# Mainboard.net
KiCad netlist of a schematic drawn in Altium Designer
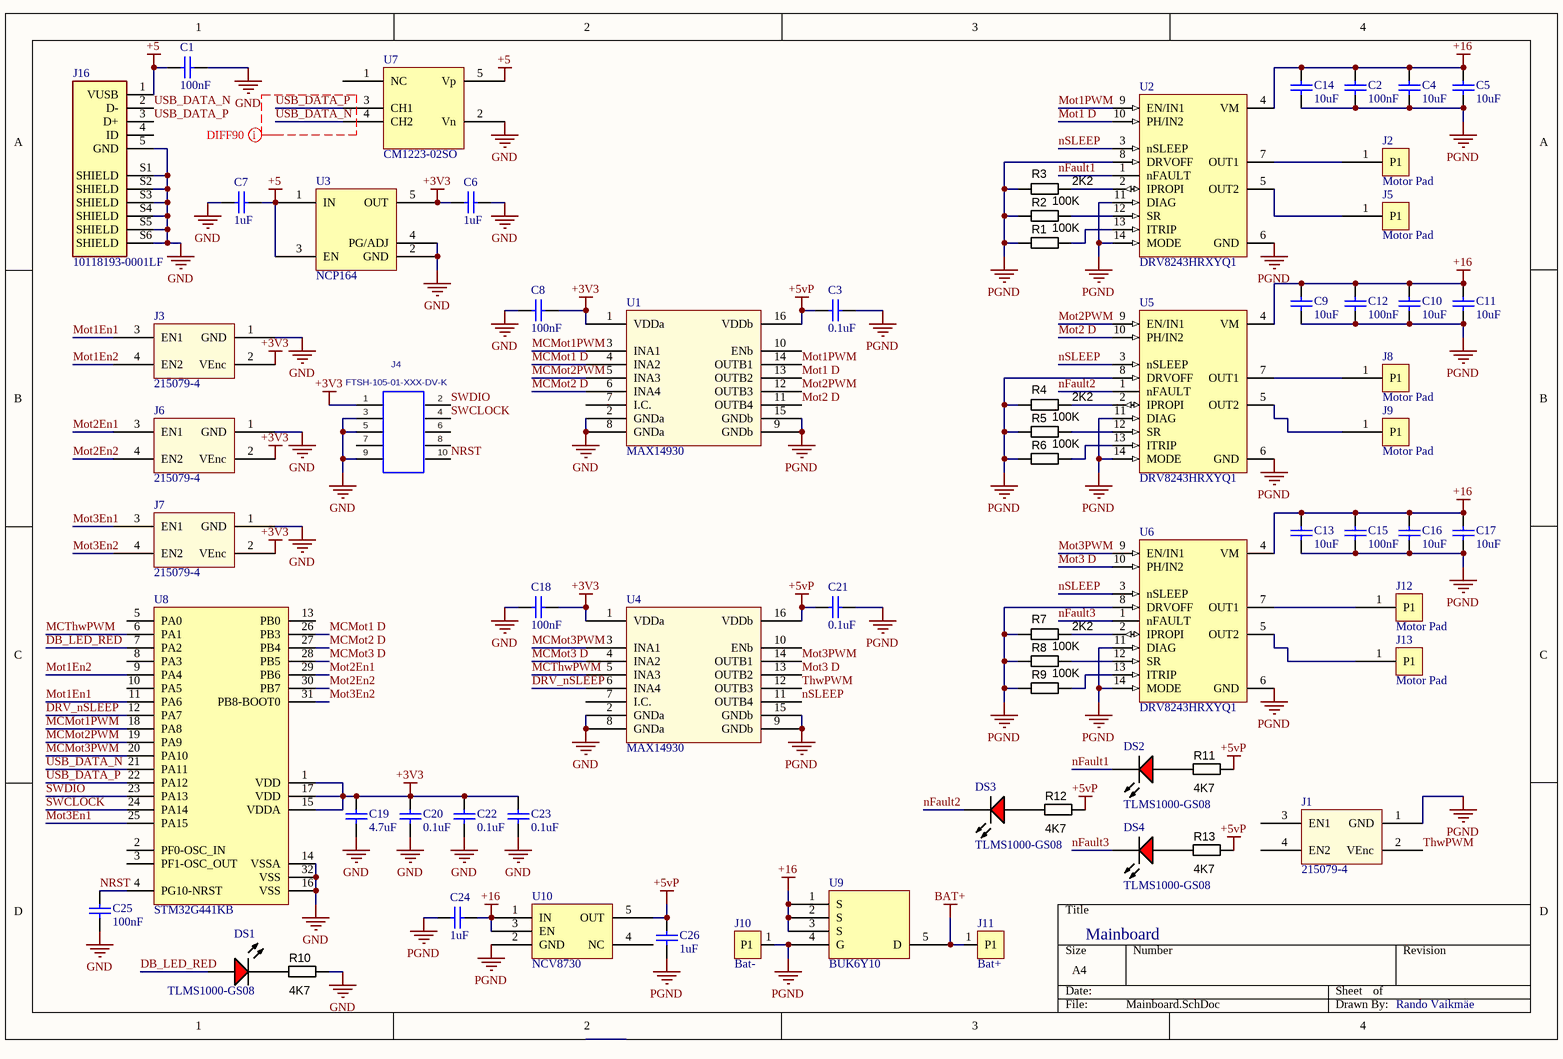
[diagram p0: Mainboard.SchDoc]

(export (version "E")
  (design (tool "Eeschema 10.0.6"))
  (components
    (comp (ref "C1")
      (value "100nF")
      (footprint "1608[0603]")
      (description "Capacitor (Semiconductor SIM Model)")
      (fields (field (name "Comment") "Cap Semi") (field (name "PUBLISHER") "Altium Limited"))
      (libsource (lib "Miscellaneous Devices") (part "Cap Semi"))
    )
    (comp (ref "C2")
      (value "100nF")
      (footprint "1608[0603]")
      (description "Capacitor (Semiconductor SIM Model)")
      (fields (field (name "Comment") "Cap Semi") (field (name "PUBLISHER") "Altium Limited"))
      (libsource (lib "Miscellaneous Devices") (part "Cap Semi"))
    )
    (comp (ref "C3")
      (value "0.1uF")
      (footprint "1608[0603]")
      (description "Capacitor (Semiconductor SIM Model)")
      (fields (field (name "Comment") "Cap Semi") (field (name "PUBLISHER") "Altium Limited"))
      (libsource (lib "Miscellaneous Devices") (part "Cap Semi"))
    )
    (comp (ref "C4")
      (value "10uF")
      (footprint "C1206")
      (description "Capacitor (Semiconductor SIM Model)")
      (fields (field (name "Comment") "Cap Semi") (field (name "PUBLISHER") "Altium Limited"))
      (libsource (lib "Miscellaneous Devices") (part "Cap Semi"))
    )
    (comp (ref "C5")
      (value "10uF")
      (footprint "C1206")
      (description "Capacitor (Semiconductor SIM Model)")
      (fields (field (name "Comment") "Cap Semi") (field (name "PUBLISHER") "Altium Limited"))
      (libsource (lib "Miscellaneous Devices") (part "Cap Semi"))
    )
    (comp (ref "C6")
      (value "1uF")
      (footprint "1608[0603]")
      (description "Capacitor (Semiconductor SIM Model)")
      (fields (field (name "Comment") "Cap Semi") (field (name "PUBLISHER") "Altium Limited"))
      (libsource (lib "Miscellaneous Devices") (part "Cap Semi"))
    )
    (comp (ref "C7")
      (value "1uF")
      (footprint "1608[0603]")
      (description "Capacitor (Semiconductor SIM Model)")
      (fields (field (name "Comment") "Cap Semi") (field (name "PUBLISHER") "Altium Limited"))
      (libsource (lib "Miscellaneous Devices") (part "Cap Semi"))
    )
    (comp (ref "C8")
      (value "100nF")
      (footprint "1608[0603]")
      (description "Capacitor (Semiconductor SIM Model)")
      (fields (field (name "Comment") "Cap Semi") (field (name "PUBLISHER") "Altium Limited"))
      (libsource (lib "Miscellaneous Devices") (part "Cap Semi"))
    )
    (comp (ref "C9")
      (value "10uF")
      (footprint "C1206")
      (description "Capacitor (Semiconductor SIM Model)")
      (fields (field (name "Comment") "Cap Semi") (field (name "PUBLISHER") "Altium Limited"))
      (libsource (lib "Miscellaneous Devices") (part "Cap Semi"))
    )
    (comp (ref "C10")
      (value "10uF")
      (footprint "C1206")
      (description "Capacitor (Semiconductor SIM Model)")
      (fields (field (name "Comment") "Cap Semi") (field (name "PUBLISHER") "Altium Limited"))
      (libsource (lib "Miscellaneous Devices") (part "Cap Semi"))
    )
    (comp (ref "C11")
      (value "10uF")
      (footprint "C1206")
      (description "Capacitor (Semiconductor SIM Model)")
      (fields (field (name "Comment") "Cap Semi") (field (name "PUBLISHER") "Altium Limited"))
      (libsource (lib "Miscellaneous Devices") (part "Cap Semi"))
    )
    (comp (ref "C12")
      (value "100nF")
      (footprint "1608[0603]")
      (description "Capacitor (Semiconductor SIM Model)")
      (fields (field (name "Comment") "Cap Semi") (field (name "PUBLISHER") "Altium Limited"))
      (libsource (lib "Miscellaneous Devices") (part "Cap Semi"))
    )
    (comp (ref "C13")
      (value "10uF")
      (footprint "C1206")
      (description "Capacitor (Semiconductor SIM Model)")
      (fields (field (name "Comment") "Cap Semi") (field (name "PUBLISHER") "Altium Limited"))
      (libsource (lib "Miscellaneous Devices") (part "Cap Semi"))
    )
    (comp (ref "C14")
      (value "10uF")
      (footprint "C1206")
      (description "Capacitor (Semiconductor SIM Model)")
      (fields (field (name "Comment") "Cap Semi") (field (name "PUBLISHER") "Altium Limited"))
      (libsource (lib "Miscellaneous Devices") (part "Cap Semi"))
    )
    (comp (ref "C15")
      (value "100nF")
      (footprint "1608[0603]")
      (description "Capacitor (Semiconductor SIM Model)")
      (fields (field (name "Comment") "Cap Semi") (field (name "PUBLISHER") "Altium Limited"))
      (libsource (lib "Miscellaneous Devices") (part "Cap Semi"))
    )
    (comp (ref "C16")
      (value "10uF")
      (footprint "C1206")
      (description "Capacitor (Semiconductor SIM Model)")
      (fields (field (name "Comment") "Cap Semi") (field (name "PUBLISHER") "Altium Limited"))
      (libsource (lib "Miscellaneous Devices") (part "Cap Semi"))
    )
    (comp (ref "C17")
      (value "10uF")
      (footprint "C1206")
      (description "Capacitor (Semiconductor SIM Model)")
      (fields (field (name "Comment") "Cap Semi") (field (name "PUBLISHER") "Altium Limited"))
      (libsource (lib "Miscellaneous Devices") (part "Cap Semi"))
    )
    (comp (ref "C18")
      (value "100nF")
      (footprint "1608[0603]")
      (description "Capacitor (Semiconductor SIM Model)")
      (fields (field (name "Comment") "Cap Semi") (field (name "PUBLISHER") "Altium Limited"))
      (libsource (lib "Miscellaneous Devices") (part "Cap Semi"))
    )
    (comp (ref "C19")
      (value "4.7uF")
      (footprint "1608[0603]")
      (description "Capacitor (Semiconductor SIM Model)")
      (fields (field (name "Comment") "Cap Semi") (field (name "PUBLISHER") "Altium Limited"))
      (libsource (lib "Miscellaneous Devices") (part "Cap Semi"))
    )
    (comp (ref "C20")
      (value "0.1uF")
      (footprint "1608[0603]")
      (description "Capacitor (Semiconductor SIM Model)")
      (fields (field (name "Comment") "Cap Semi") (field (name "PUBLISHER") "Altium Limited"))
      (libsource (lib "Miscellaneous Devices") (part "Cap Semi"))
    )
    (comp (ref "C21")
      (value "0.1uF")
      (footprint "1608[0603]")
      (description "Capacitor (Semiconductor SIM Model)")
      (fields (field (name "Comment") "Cap Semi") (field (name "PUBLISHER") "Altium Limited"))
      (libsource (lib "Miscellaneous Devices") (part "Cap Semi"))
    )
    (comp (ref "C22")
      (value "0.1uF")
      (footprint "1608[0603]")
      (description "Capacitor (Semiconductor SIM Model)")
      (fields (field (name "Comment") "Cap Semi") (field (name "PUBLISHER") "Altium Limited"))
      (libsource (lib "Miscellaneous Devices") (part "Cap Semi"))
    )
    (comp (ref "C23")
      (value "0.1uF")
      (footprint "1608[0603]")
      (description "Capacitor (Semiconductor SIM Model)")
      (fields (field (name "Comment") "Cap Semi") (field (name "PUBLISHER") "Altium Limited"))
      (libsource (lib "Miscellaneous Devices") (part "Cap Semi"))
    )
    (comp (ref "C24")
      (value "1uF")
      (footprint "1608[0603]")
      (description "Capacitor (Semiconductor SIM Model)")
      (fields (field (name "Comment") "Cap Semi") (field (name "PUBLISHER") "Altium Limited"))
      (libsource (lib "Miscellaneous Devices") (part "Cap Semi"))
    )
    (comp (ref "C25")
      (value "100nF")
      (footprint "1608[0603]")
      (description "Capacitor (Semiconductor SIM Model)")
      (fields (field (name "Comment") "Cap Semi") (field (name "PUBLISHER") "Altium Limited"))
      (libsource (lib "Miscellaneous Devices") (part "Cap Semi"))
    )
    (comp (ref "C26")
      (value "1uF")
      (footprint "1608[0603]")
      (description "Capacitor (Semiconductor SIM Model)")
      (fields (field (name "Comment") "Cap Semi") (field (name "PUBLISHER") "Altium Limited"))
      (libsource (lib "Miscellaneous Devices") (part "Cap Semi"))
    )
    (comp (ref "DS1")
      (value "TLMS1000-GS08")
      (footprint "VISH-TLMS1000_V")
      (description "Low Current LED, 40 mW, 1.8 V, -40 to 100 degC, 2-Pin SMD (0603), RoHS, Tape and Reel")
      (fields (field (name "MANUFACTURER") "Vishay"))
      (libsource (lib "Altium Content Vault") (part "LED-RED-AK-2"))
    )
    (comp (ref "DS2")
      (value "TLMS1000-GS08")
      (footprint "VISH-TLMS1000_V")
      (description "Low Current LED, 40 mW, 1.8 V, -40 to 100 degC, 2-Pin SMD (0603), RoHS, Tape and Reel")
      (fields (field (name "MANUFACTURER") "Vishay"))
      (libsource (lib "Altium Content Vault") (part "LED-RED-AK-2"))
    )
    (comp (ref "DS3")
      (value "TLMS1000-GS08")
      (footprint "VISH-TLMS1000_V")
      (description "Low Current LED, 40 mW, 1.8 V, -40 to 100 degC, 2-Pin SMD (0603), RoHS, Tape and Reel")
      (fields (field (name "MANUFACTURER") "Vishay"))
      (libsource (lib "Altium Content Vault") (part "LED-RED-AK-2"))
    )
    (comp (ref "DS4")
      (value "TLMS1000-GS08")
      (footprint "VISH-TLMS1000_V")
      (description "Low Current LED, 40 mW, 1.8 V, -40 to 100 degC, 2-Pin SMD (0603), RoHS, Tape and Reel")
      (fields (field (name "MANUFACTURER") "Vishay"))
      (libsource (lib "Altium Content Vault") (part "LED-RED-AK-2"))
    )
    (comp (ref "J1")
      (value "215079-4")
      (footprint "MICRO-MATCH-FOB-04")
      (description "Micro-MaTch 215079-4")
      (libsource (lib "215079-4") (part "215079-4"))
    )
    (comp (ref "J2")
      (value "Motor Pad")
      (footprint "motorPads")
      (description "Motor pad")
      (libsource (lib "Motorpad") (part "Motor Pad"))
    )
    (comp (ref "J3")
      (value "215079-4")
      (footprint "MICRO-MATCH-FOB-04")
      (description "Micro-MaTch 215079-4")
      (libsource (lib "215079-4") (part "215079-4"))
    )
    (comp (ref "J4")
      (value "FTSH-105-01-XXX-DV-K")
      (footprint "FTSH-105-01-XXX-DV-K")
      (description "TERMINAL STRIP, .050\"(1.27mm) PITCH, 10 PINS, KEYED")
      (fields (field (name "MANUFACTURER") "SAMTEC") (field (name "CREATED") "November 30, 2016 - Wendy Xin"))
      (libsource (lib "FTSH-105-01-XXX-DV-K") (part "FTSH-105-01-XXX-DV-K"))
    )
    (comp (ref "J5")
      (value "Motor Pad")
      (footprint "motorPads")
      (description "Motor pad")
      (libsource (lib "Motorpad") (part "Motor Pad"))
    )
    (comp (ref "J6")
      (value "215079-4")
      (footprint "MICRO-MATCH-FOB-04")
      (description "Micro-MaTch 215079-4")
      (libsource (lib "215079-4") (part "215079-4"))
    )
    (comp (ref "J7")
      (value "215079-4")
      (footprint "MICRO-MATCH-FOB-04")
      (description "Micro-MaTch 215079-4")
      (libsource (lib "215079-4") (part "215079-4"))
    )
    (comp (ref "J8")
      (value "Motor Pad")
      (footprint "motorPads")
      (description "Motor pad")
      (libsource (lib "Motorpad") (part "Motor Pad"))
    )
    (comp (ref "J9")
      (value "Motor Pad")
      (footprint "motorPads")
      (description "Motor pad")
      (libsource (lib "Motorpad") (part "Motor Pad"))
    )
    (comp (ref "J10")
      (value "Bat-")
      (footprint "motorPads")
      (description "Batteryterminal")
      (libsource (lib "Batteryterminal") (part "Bat"))
    )
    (comp (ref "J11")
      (value "Bat+")
      (footprint "motorPads")
      (description "Batteryterminal")
      (libsource (lib "") (part "Bat_1"))
    )
    (comp (ref "J12")
      (value "Motor Pad")
      (footprint "motorPads")
      (description "Motor pad")
      (libsource (lib "Motorpad") (part "Motor Pad"))
    )
    (comp (ref "J13")
      (value "Motor Pad")
      (footprint "motorPads")
      (description "Motor pad")
      (libsource (lib "Motorpad") (part "Motor Pad"))
    )
    (comp (ref "J16")
      (value "10118193-0001LF")
      (footprint "FCI_10118193-0001LF")
      (description "USB - micro B USB 2.0 Receptacle Connector 5 Position Surface Mount, Right Angle; Through Hole")
      (fields (field (name "MF") "Amphenol ICC"))
      (libsource (lib "SnapEDAsch") (part "10118193-0001LF"))
    )
    (comp (ref "R1")
      (value "100K")
      (footprint "RESC1608X55N")
      (description "Resistor SMD chip 100k Ohm 0.1W 1% 0603")
      (fields (field (name "TOLERANCE") "±1%") (field (name "Comment") "Thick Film"))
      (libsource (lib "PBL - Resistors") (part "RES_100K_0603_1%"))
    )
    (comp (ref "R2")
      (value "100K")
      (footprint "RESC1608X55N")
      (description "Resistor SMD chip 100k Ohm 0.1W 1% 0603")
      (fields (field (name "TOLERANCE") "±1%") (field (name "Comment") "Thick Film"))
      (libsource (lib "PBL - Resistors") (part "RES_100K_0603_1%"))
    )
    (comp (ref "R3")
      (value "2K2")
      (footprint "RESC1608X55N")
      (description "Resistor SMD chip 2.2k Ohm 0.1W 5% 0603")
      (fields (field (name "TOLERANCE") "±5%") (field (name "Comment") "Thick Film"))
      (libsource (lib "PBL - Resistors") (part "RES_2K2_0603_5%"))
    )
    (comp (ref "R4")
      (value "2K2")
      (footprint "RESC1608X55N")
      (description "Resistor SMD chip 2.2k Ohm 0.1W 5% 0603")
      (fields (field (name "TOLERANCE") "±5%") (field (name "Comment") "Thick Film"))
      (libsource (lib "PBL - Resistors") (part "RES_2K2_0603_5%"))
    )
    (comp (ref "R5")
      (value "100K")
      (footprint "RESC1608X55N")
      (description "Resistor SMD chip 100k Ohm 0.1W 1% 0603")
      (fields (field (name "TOLERANCE") "±1%") (field (name "Comment") "Thick Film"))
      (libsource (lib "PBL - Resistors") (part "RES_100K_0603_1%"))
    )
    (comp (ref "R6")
      (value "100K")
      (footprint "RESC1608X55N")
      (description "Resistor SMD chip 100k Ohm 0.1W 1% 0603")
      (fields (field (name "TOLERANCE") "±1%") (field (name "Comment") "Thick Film"))
      (libsource (lib "PBL - Resistors") (part "RES_100K_0603_1%"))
    )
    (comp (ref "R7")
      (value "2K2")
      (footprint "RESC1608X55N")
      (description "Resistor SMD chip 2.2k Ohm 0.1W 5% 0603")
      (fields (field (name "TOLERANCE") "±5%") (field (name "Comment") "Thick Film"))
      (libsource (lib "PBL - Resistors") (part "RES_2K2_0603_5%"))
    )
    (comp (ref "R8")
      (value "100K")
      (footprint "RESC1608X55N")
      (description "Resistor SMD chip 100k Ohm 0.1W 1% 0603")
      (fields (field (name "TOLERANCE") "±1%") (field (name "Comment") "Thick Film"))
      (libsource (lib "PBL - Resistors") (part "RES_100K_0603_1%"))
    )
    (comp (ref "R9")
      (value "100K")
      (footprint "RESC1608X55N")
      (description "Resistor SMD chip 100k Ohm 0.1W 1% 0603")
      (fields (field (name "TOLERANCE") "±1%") (field (name "Comment") "Thick Film"))
      (libsource (lib "PBL - Resistors") (part "RES_100K_0603_1%"))
    )
    (comp (ref "R10")
      (value "4K7")
      (footprint "RESC1608X55N")
      (description "Resistor SMD chip 4.7K Ohm 0.1W 1% 0603")
      (fields
        (field (name "MANUFACTURER") "Yageo")
        (field (name "MANUFACTURER PART NUMBER") "RC0603FR-074K7L")
      )
      (libsource (lib "PBL - Resistors") (part "RES_4K7_0603_1%"))
    )
    (comp (ref "R11")
      (value "4K7")
      (footprint "RESC1608X55N")
      (description "Resistor SMD chip 4.7K Ohm 0.1W 1% 0603")
      (fields
        (field (name "MANUFACTURER") "Yageo")
        (field (name "MANUFACTURER PART NUMBER") "RC0603FR-074K7L")
      )
      (libsource (lib "PBL - Resistors") (part "RES_4K7_0603_1%"))
    )
    (comp (ref "R12")
      (value "4K7")
      (footprint "RESC1608X55N")
      (description "Resistor SMD chip 4.7K Ohm 0.1W 1% 0603")
      (fields
        (field (name "MANUFACTURER") "Yageo")
        (field (name "MANUFACTURER PART NUMBER") "RC0603FR-074K7L")
      )
      (libsource (lib "PBL - Resistors") (part "RES_4K7_0603_1%"))
    )
    (comp (ref "R13")
      (value "4K7")
      (footprint "RESC1608X55N")
      (description "Resistor SMD chip 4.7K Ohm 0.1W 1% 0603")
      (fields
        (field (name "MANUFACTURER") "Yageo")
        (field (name "MANUFACTURER PART NUMBER") "RC0603FR-074K7L")
      )
      (libsource (lib "PBL - Resistors") (part "RES_4K7_0603_1%"))
    )
    (comp (ref "U1")
      (value "MAX14930")
      (footprint "SOIC127P600X175-16N")
      (description "MAX14930DASE+")
      (libsource (lib "MAX14930") (part "MAX14930"))
    )
    (comp (ref "U2")
      (value "DRV8243HRXYQ1")
      (footprint "DRV8243_VQFN-HR_14")
      (description "Automotive H-Bridge Driver with Integrated Current Sense and Diagnostics")
      (libsource (lib "texas_instruments") (part "DRV8243H-Q1_VQFN-HR_14"))
    )
    (comp (ref "U3")
      (value "NCP164")
      (footprint "SOT95P275X110-5N")
      (description "NCP164CSN330T1G")
      (libsource (lib "NCP164") (part "NCP164"))
    )
    (comp (ref "U4")
      (value "MAX14930")
      (footprint "SOIC127P600X175-16N")
      (description "MAX14930DASE+")
      (libsource (lib "MAX14930") (part "MAX14930"))
    )
    (comp (ref "U5")
      (value "DRV8243HRXYQ1")
      (footprint "DRV8243_VQFN-HR_14")
      (description "Automotive H-Bridge Driver with Integrated Current Sense and Diagnostics")
      (libsource (lib "texas_instruments") (part "DRV8243H-Q1_VQFN-HR_14"))
    )
    (comp (ref "U6")
      (value "DRV8243HRXYQ1")
      (footprint "DRV8243_VQFN-HR_14")
      (description "Automotive H-Bridge Driver with Integrated Current Sense and Diagnostics")
      (libsource (lib "texas_instruments") (part "DRV8243H-Q1_VQFN-HR_14"))
    )
    (comp (ref "U7")
      (value "CM1223-02SO")
      (footprint "SOT95P275X110-5N")
      (description "CM1223-02SO TVS diode array")
      (libsource (lib "CM1223-2SO") (part "CM1223-02SO"))
    )
    (comp (ref "U8")
      (value "STM32G441KB")
      (footprint "TQFP80P900X900X160-32N")
      (libsource (lib "STM32G441KB") (part "STM32G441KB"))
    )
    (comp (ref "U9")
      (value "BUK6Y10")
      (footprint "TO127P600X120-5N")
      (description "BUK6Y10-30PX")
      (libsource (lib "BUK6Y10") (part "BUK6Y10"))
    )
    (comp (ref "U10")
      (value "NCV8730")
      (footprint "SOT95P275X110-5N")
      (description "NCV8730ASN500T1G")
      (libsource (lib "NCV8730") (part "NCV8730"))
    )
  )
  (nets
    (net (code "1") (name "+3V3") (class "Default")
      (node (ref "C18") (pin "1") (pinfunction "1_1") (pintype "passive"))
      (node (ref "C19") (pin "2") (pinfunction "2_2") (pintype "passive"))
      (node (ref "C20") (pin "2") (pinfunction "2_2") (pintype "passive"))
      (node (ref "C22") (pin "2") (pinfunction "2_2") (pintype "passive"))
      (node (ref "C23") (pin "2") (pinfunction "2_2") (pintype "passive"))
      (node (ref "C6") (pin "2") (pinfunction "2_2") (pintype "passive"))
      (node (ref "C8") (pin "1") (pinfunction "1_1") (pintype "passive"))
      (node (ref "J3") (pin "2") (pinfunction "VEnc_2") (pintype "passive"))
      (node (ref "J4") (pin "1") (pintype "passive"))
      (node (ref "J6") (pin "2") (pinfunction "VEnc_2") (pintype "passive"))
      (node (ref "J7") (pin "2") (pinfunction "VEnc_2") (pintype "passive"))
      (node (ref "U1") (pin "1") (pinfunction "VDDa_1") (pintype "passive"))
      (node (ref "U3") (pin "5") (pinfunction "OUT_5") (pintype "passive"))
      (node (ref "U4") (pin "1") (pinfunction "VDDa_1") (pintype "passive"))
      (node (ref "U8") (pin "1") (pinfunction "VDD_1") (pintype "passive"))
      (node (ref "U8") (pin "15") (pinfunction "VDDA_15") (pintype "passive"))
      (node (ref "U8") (pin "17") (pinfunction "VDD_17") (pintype "passive"))
    )
    (net (code "2") (name "+5") (class "Default")
      (node (ref "C1") (pin "2") (pinfunction "2_2") (pintype "passive"))
      (node (ref "C7") (pin "1") (pinfunction "1_1") (pintype "passive"))
      (node (ref "J16") (pin "1") (pinfunction "VUSB_1") (pintype "passive"))
      (node (ref "U3") (pin "1") (pinfunction "IN_1") (pintype "passive"))
      (node (ref "U3") (pin "3") (pinfunction "EN_3") (pintype "passive"))
      (node (ref "U7") (pin "5") (pinfunction "Vp_5") (pintype "passive"))
    )
    (net (code "3") (name "+5vP") (class "Default")
      (node (ref "C21") (pin "2") (pinfunction "2_2") (pintype "passive"))
      (node (ref "C26") (pin "2") (pinfunction "2_2") (pintype "passive"))
      (node (ref "C3") (pin "2") (pinfunction "2_2") (pintype "passive"))
      (node (ref "R11") (pin "2") (pinfunction "2_2") (pintype "passive"))
      (node (ref "R12") (pin "2") (pinfunction "2_2") (pintype "passive"))
      (node (ref "R13") (pin "2") (pinfunction "2_2") (pintype "passive"))
      (node (ref "U1") (pin "16") (pinfunction "VDDb_16") (pintype "passive"))
      (node (ref "U10") (pin "5") (pinfunction "OUT_5") (pintype "passive"))
      (node (ref "U4") (pin "16") (pinfunction "VDDb_16") (pintype "passive"))
    )
    (net (code "4") (name "+16") (class "Default")
      (node (ref "C10") (pin "2") (pinfunction "2_2") (pintype "passive"))
      (node (ref "C11") (pin "2") (pinfunction "2_2") (pintype "passive"))
      (node (ref "C12") (pin "2") (pinfunction "2_2") (pintype "passive"))
      (node (ref "C13") (pin "2") (pinfunction "2_2") (pintype "passive"))
      (node (ref "C14") (pin "2") (pinfunction "2_2") (pintype "passive"))
      (node (ref "C15") (pin "2") (pinfunction "2_2") (pintype "passive"))
      (node (ref "C16") (pin "2") (pinfunction "2_2") (pintype "passive"))
      (node (ref "C17") (pin "2") (pinfunction "2_2") (pintype "passive"))
      (node (ref "C2") (pin "2") (pinfunction "2_2") (pintype "passive"))
      (node (ref "C24") (pin "1") (pinfunction "1_1") (pintype "passive"))
      (node (ref "C4") (pin "2") (pinfunction "2_2") (pintype "passive"))
      (node (ref "C5") (pin "2") (pinfunction "2_2") (pintype "passive"))
      (node (ref "C9") (pin "2") (pinfunction "2_2") (pintype "passive"))
      (node (ref "U10") (pin "1") (pinfunction "IN_1") (pintype "passive"))
      (node (ref "U10") (pin "3") (pinfunction "EN_3") (pintype "passive"))
      (node (ref "U2") (pin "4") (pinfunction "VM_4") (pintype "power_in"))
      (node (ref "U5") (pin "4") (pinfunction "VM_4") (pintype "power_in"))
      (node (ref "U6") (pin "4") (pinfunction "VM_4") (pintype "power_in"))
      (node (ref "U9") (pin "1") (pinfunction "S_1") (pintype "passive"))
      (node (ref "U9") (pin "2") (pinfunction "S_2") (pintype "passive"))
      (node (ref "U9") (pin "3") (pinfunction "S_3") (pintype "passive"))
    )
    (net (code "5") (name "/DB_LED_RED") (class "Default")
      (node (ref "DS1") (pin "1") (pinfunction "A_1") (pintype "passive"))
      (node (ref "U8") (pin "7") (pinfunction "PA2_7") (pintype "passive"))
    )
    (net (code "6") (name "/DRV_nSLEEP") (class "Default")
      (node (ref "U4") (pin "6") (pinfunction "INA4_6") (pintype "passive"))
      (node (ref "U8") (pin "12") (pinfunction "PA7_12") (pintype "passive"))
    )
    (net (code "7") (name "/MCMot1 D") (class "Default")
      (node (ref "U1") (pin "4") (pinfunction "INA2_4") (pintype "passive"))
      (node (ref "U8") (pin "26") (pinfunction "PB3_26") (pintype "passive"))
    )
    (net (code "8") (name "/MCMot1PWM") (class "Default")
      (node (ref "U1") (pin "3") (pinfunction "INA1_3") (pintype "passive"))
      (node (ref "U8") (pin "18") (pinfunction "PA8_18") (pintype "passive"))
    )
    (net (code "9") (name "/MCMot2 D") (class "Default")
      (node (ref "U1") (pin "6") (pinfunction "INA4_6") (pintype "passive"))
      (node (ref "U8") (pin "27") (pinfunction "PB4_27") (pintype "passive"))
    )
    (net (code "10") (name "/MCMot2PWM") (class "Default")
      (node (ref "U1") (pin "5") (pinfunction "INA3_5") (pintype "passive"))
      (node (ref "U8") (pin "19") (pinfunction "PA9_19") (pintype "passive"))
    )
    (net (code "11") (name "/MCMot3 D") (class "Default")
      (node (ref "U4") (pin "4") (pinfunction "INA2_4") (pintype "passive"))
      (node (ref "U8") (pin "28") (pinfunction "PB5_28") (pintype "passive"))
    )
    (net (code "12") (name "/MCMot3PWM") (class "Default")
      (node (ref "U4") (pin "3") (pinfunction "INA1_3") (pintype "passive"))
      (node (ref "U8") (pin "20") (pinfunction "PA10_20") (pintype "passive"))
    )
    (net (code "13") (name "/MCThwPWM") (class "Default")
      (node (ref "U4") (pin "5") (pinfunction "INA3_5") (pintype "passive"))
      (node (ref "U8") (pin "6") (pinfunction "PA1_6") (pintype "passive"))
    )
    (net (code "14") (name "/Mot1 D") (class "Default")
      (node (ref "U1") (pin "13") (pinfunction "OUTB2_13") (pintype "passive"))
      (node (ref "U2") (pin "10") (pinfunction "PH/IN2_10") (pintype "input"))
    )
    (net (code "15") (name "/Mot1En1") (class "Default")
      (node (ref "J3") (pin "3") (pinfunction "EN1_3") (pintype "passive"))
      (node (ref "U8") (pin "11") (pinfunction "PA6_11") (pintype "passive"))
    )
    (net (code "16") (name "/Mot1En2") (class "Default")
      (node (ref "J3") (pin "4") (pinfunction "EN2_4") (pintype "passive"))
      (node (ref "U8") (pin "9") (pinfunction "PA4_9") (pintype "passive"))
    )
    (net (code "17") (name "/Mot1PWM") (class "Default")
      (node (ref "U1") (pin "14") (pinfunction "OUTB1_14") (pintype "passive"))
      (node (ref "U2") (pin "9") (pinfunction "EN/IN1_9") (pintype "input"))
    )
    (net (code "18") (name "/Mot2 D") (class "Default")
      (node (ref "U1") (pin "11") (pinfunction "OUTB4_11") (pintype "passive"))
      (node (ref "U5") (pin "10") (pinfunction "PH/IN2_10") (pintype "input"))
    )
    (net (code "19") (name "/Mot2En1") (class "Default")
      (node (ref "J6") (pin "3") (pinfunction "EN1_3") (pintype "passive"))
      (node (ref "U8") (pin "29") (pinfunction "PB6_29") (pintype "passive"))
    )
    (net (code "20") (name "/Mot2En2") (class "Default")
      (node (ref "J6") (pin "4") (pinfunction "EN2_4") (pintype "passive"))
      (node (ref "U8") (pin "30") (pinfunction "PB7_30") (pintype "passive"))
    )
    (net (code "21") (name "/Mot2PWM") (class "Default")
      (node (ref "U1") (pin "12") (pinfunction "OUTB3_12") (pintype "passive"))
      (node (ref "U5") (pin "9") (pinfunction "EN/IN1_9") (pintype "input"))
    )
    (net (code "22") (name "/Mot3 D") (class "Default")
      (node (ref "U4") (pin "13") (pinfunction "OUTB2_13") (pintype "passive"))
      (node (ref "U6") (pin "10") (pinfunction "PH/IN2_10") (pintype "input"))
    )
    (net (code "23") (name "/Mot3En1") (class "Default")
      (node (ref "J7") (pin "3") (pinfunction "EN1_3") (pintype "passive"))
      (node (ref "U8") (pin "25") (pinfunction "PA15_25") (pintype "passive"))
    )
    (net (code "24") (name "/Mot3En2") (class "Default")
      (node (ref "J7") (pin "4") (pinfunction "EN2_4") (pintype "passive"))
      (node (ref "U8") (pin "31") (pinfunction "PB8-BOOT0_31") (pintype "passive"))
    )
    (net (code "25") (name "/Mot3PWM") (class "Default")
      (node (ref "U4") (pin "14") (pinfunction "OUTB1_14") (pintype "passive"))
      (node (ref "U6") (pin "9") (pinfunction "EN/IN1_9") (pintype "input"))
    )
    (net (code "26") (name "/NRST") (class "Default")
      (node (ref "C25") (pin "1") (pinfunction "1_1") (pintype "passive"))
      (node (ref "J4") (pin "10") (pintype "passive"))
      (node (ref "U8") (pin "4") (pinfunction "PG10-NRST_4") (pintype "passive"))
    )
    (net (code "27") (name "/SWCLOCK") (class "Default")
      (node (ref "J4") (pin "4") (pintype "passive"))
      (node (ref "U8") (pin "24") (pinfunction "PA14_24") (pintype "passive"))
    )
    (net (code "28") (name "/SWDIO") (class "Default")
      (node (ref "J4") (pin "2") (pintype "passive"))
      (node (ref "U8") (pin "23") (pinfunction "PA13_23") (pintype "passive"))
    )
    (net (code "29") (name "/ThwPWM") (class "Default")
      (node (ref "J1") (pin "2") (pinfunction "VEnc_2") (pintype "passive"))
      (node (ref "U4") (pin "12") (pinfunction "OUTB3_12") (pintype "passive"))
    )
    (net (code "30") (name "/USB_DATA_N") (class "Default")
      (node (ref "J16") (pin "2") (pinfunction "D-_2") (pintype "passive"))
      (node (ref "U7") (pin "4") (pinfunction "CH2_4") (pintype "passive"))
      (node (ref "U8") (pin "21") (pinfunction "PA11_21") (pintype "passive"))
    )
    (net (code "31") (name "/USB_DATA_P") (class "Default")
      (node (ref "J16") (pin "3") (pinfunction "D+_3") (pintype "passive"))
      (node (ref "U7") (pin "3") (pinfunction "CH1_3") (pintype "passive"))
      (node (ref "U8") (pin "22") (pinfunction "PA12_22") (pintype "passive"))
    )
    (net (code "32") (name "/nFault1") (class "Default")
      (node (ref "DS2") (pin "2") (pinfunction "K_2") (pintype "passive"))
      (node (ref "U2") (pin "1") (pinfunction "nFAULT_1") (pintype "open_collector"))
    )
    (net (code "33") (name "/nFault2") (class "Default")
      (node (ref "DS3") (pin "2") (pinfunction "K_2") (pintype "passive"))
      (node (ref "U5") (pin "1") (pinfunction "nFAULT_1") (pintype "open_collector"))
    )
    (net (code "34") (name "/nFault3") (class "Default")
      (node (ref "DS4") (pin "2") (pinfunction "K_2") (pintype "passive"))
      (node (ref "U6") (pin "1") (pinfunction "nFAULT_1") (pintype "open_collector"))
    )
    (net (code "35") (name "/nSLEEP") (class "Default")
      (node (ref "U2") (pin "3") (pinfunction "nSLEEP_3") (pintype "input"))
      (node (ref "U4") (pin "11") (pinfunction "OUTB4_11") (pintype "passive"))
      (node (ref "U5") (pin "3") (pinfunction "nSLEEP_3") (pintype "input"))
      (node (ref "U6") (pin "3") (pinfunction "nSLEEP_3") (pintype "input"))
    )
    (net (code "36") (name "BAT+") (class "Default")
      (node (ref "J11") (pin "1") (pinfunction "P1_1") (pintype "passive"))
      (node (ref "U9") (pin "5") (pinfunction "D_5") (pintype "passive"))
    )
    (net (code "37") (name "GND") (class "Default")
      (node (ref "C1") (pin "1") (pinfunction "1_1") (pintype "passive"))
      (node (ref "C18") (pin "2") (pinfunction "2_2") (pintype "passive"))
      (node (ref "C19") (pin "1") (pinfunction "1_1") (pintype "passive"))
      (node (ref "C20") (pin "1") (pinfunction "1_1") (pintype "passive"))
      (node (ref "C22") (pin "1") (pinfunction "1_1") (pintype "passive"))
      (node (ref "C23") (pin "1") (pinfunction "1_1") (pintype "passive"))
      (node (ref "C25") (pin "2") (pinfunction "2_2") (pintype "passive"))
      (node (ref "C6") (pin "1") (pinfunction "1_1") (pintype "passive"))
      (node (ref "C7") (pin "2") (pinfunction "2_2") (pintype "passive"))
      (node (ref "C8") (pin "2") (pinfunction "2_2") (pintype "passive"))
      (node (ref "J16") (pin "5") (pinfunction "GND_5") (pintype "passive"))
      (node (ref "J16") (pin "S1") (pinfunction "SHIELD_S1") (pintype "passive"))
      (node (ref "J16") (pin "S2") (pinfunction "SHIELD_S2") (pintype "passive"))
      (node (ref "J16") (pin "S3") (pinfunction "SHIELD_S3") (pintype "passive"))
      (node (ref "J16") (pin "S4") (pinfunction "SHIELD_S4") (pintype "passive"))
      (node (ref "J16") (pin "S5") (pinfunction "SHIELD_S5") (pintype "passive"))
      (node (ref "J16") (pin "S6") (pinfunction "SHIELD_S6") (pintype "passive"))
      (node (ref "J3") (pin "1") (pinfunction "GND_1") (pintype "passive"))
      (node (ref "J4") (pin "3") (pintype "passive"))
      (node (ref "J4") (pin "5") (pintype "passive"))
      (node (ref "J4") (pin "9") (pintype "passive"))
      (node (ref "J6") (pin "1") (pinfunction "GND_1") (pintype "passive"))
      (node (ref "J7") (pin "1") (pinfunction "GND_1") (pintype "passive"))
      (node (ref "R10") (pin "2") (pinfunction "2_2") (pintype "passive"))
      (node (ref "U1") (pin "2") (pinfunction "GNDa_2") (pintype "passive"))
      (node (ref "U1") (pin "8") (pinfunction "GNDa_8") (pintype "passive"))
      (node (ref "U3") (pin "2") (pinfunction "GND_2") (pintype "passive"))
      (node (ref "U3") (pin "4") (pinfunction "PG/ADJ_4") (pintype "passive"))
      (node (ref "U4") (pin "2") (pinfunction "GNDa_2") (pintype "passive"))
      (node (ref "U4") (pin "8") (pinfunction "GNDa_8") (pintype "passive"))
      (node (ref "U7") (pin "2") (pinfunction "Vn_2") (pintype "passive"))
      (node (ref "U8") (pin "14") (pinfunction "VSSA_14") (pintype "passive"))
      (node (ref "U8") (pin "16") (pinfunction "VSS_16") (pintype "passive"))
      (node (ref "U8") (pin "32") (pinfunction "VSS_32") (pintype "passive"))
    )
    (net (code "38") (name "Net-(DS1-K)") (class "Default")
      (node (ref "DS1") (pin "2") (pinfunction "K_2") (pintype "passive"))
      (node (ref "R10") (pin "1") (pinfunction "1_1") (pintype "passive"))
    )
    (net (code "39") (name "Net-(DS2-A)") (class "Default")
      (node (ref "DS2") (pin "1") (pinfunction "A_1") (pintype "passive"))
      (node (ref "R11") (pin "1") (pinfunction "1_1") (pintype "passive"))
    )
    (net (code "40") (name "Net-(DS3-A)") (class "Default")
      (node (ref "DS3") (pin "1") (pinfunction "A_1") (pintype "passive"))
      (node (ref "R12") (pin "1") (pinfunction "1_1") (pintype "passive"))
    )
    (net (code "41") (name "Net-(DS4-A)") (class "Default")
      (node (ref "DS4") (pin "1") (pinfunction "A_1") (pintype "passive"))
      (node (ref "R13") (pin "1") (pinfunction "1_1") (pintype "passive"))
    )
    (net (code "42") (name "Net-(J2-P1)") (class "Default")
      (node (ref "J2") (pin "1") (pinfunction "P1_1") (pintype "passive"))
      (node (ref "U2") (pin "7") (pinfunction "OUT1_7") (pintype "power_in"))
    )
    (net (code "43") (name "Net-(J5-P1)") (class "Default")
      (node (ref "J5") (pin "1") (pinfunction "P1_1") (pintype "passive"))
      (node (ref "U2") (pin "5") (pinfunction "OUT2_5") (pintype "power_in"))
    )
    (net (code "44") (name "Net-(J8-P1)") (class "Default")
      (node (ref "J8") (pin "1") (pinfunction "P1_1") (pintype "passive"))
      (node (ref "U5") (pin "7") (pinfunction "OUT1_7") (pintype "power_in"))
    )
    (net (code "45") (name "Net-(J9-P1)") (class "Default")
      (node (ref "J9") (pin "1") (pinfunction "P1_1") (pintype "passive"))
      (node (ref "U5") (pin "5") (pinfunction "OUT2_5") (pintype "power_in"))
    )
    (net (code "46") (name "Net-(J12-P1)") (class "Default")
      (node (ref "J12") (pin "1") (pinfunction "P1_1") (pintype "passive"))
      (node (ref "U6") (pin "7") (pinfunction "OUT1_7") (pintype "power_in"))
    )
    (net (code "47") (name "Net-(J13-P1)") (class "Default")
      (node (ref "J13") (pin "1") (pinfunction "P1_1") (pintype "passive"))
      (node (ref "U6") (pin "5") (pinfunction "OUT2_5") (pintype "power_in"))
    )
    (net (code "48") (name "Net-(U2-IPROPI)") (class "Default")
      (node (ref "R3") (pin "1") (pinfunction "1_1") (pintype "passive"))
      (node (ref "U2") (pin "2") (pinfunction "IPROPI_2") (pintype "bidirectional"))
    )
    (net (code "49") (name "Net-(U2-ITRIP)") (class "Default")
      (node (ref "R1") (pin "2") (pinfunction "2_2") (pintype "passive"))
      (node (ref "U2") (pin "13") (pinfunction "ITRIP_13") (pintype "input"))
    )
    (net (code "50") (name "Net-(U2-SR)") (class "Default")
      (node (ref "R2") (pin "2") (pinfunction "2_2") (pintype "passive"))
      (node (ref "U2") (pin "12") (pinfunction "SR_12") (pintype "input"))
    )
    (net (code "51") (name "Net-(U5-IPROPI)") (class "Default")
      (node (ref "R4") (pin "1") (pinfunction "1_1") (pintype "passive"))
      (node (ref "U5") (pin "2") (pinfunction "IPROPI_2") (pintype "bidirectional"))
    )
    (net (code "52") (name "Net-(U5-ITRIP)") (class "Default")
      (node (ref "R6") (pin "2") (pinfunction "2_2") (pintype "passive"))
      (node (ref "U5") (pin "13") (pinfunction "ITRIP_13") (pintype "input"))
    )
    (net (code "53") (name "Net-(U5-SR)") (class "Default")
      (node (ref "R5") (pin "2") (pinfunction "2_2") (pintype "passive"))
      (node (ref "U5") (pin "12") (pinfunction "SR_12") (pintype "input"))
    )
    (net (code "54") (name "Net-(U6-IPROPI)") (class "Default")
      (node (ref "R7") (pin "1") (pinfunction "1_1") (pintype "passive"))
      (node (ref "U6") (pin "2") (pinfunction "IPROPI_2") (pintype "bidirectional"))
    )
    (net (code "55") (name "Net-(U6-ITRIP)") (class "Default")
      (node (ref "R9") (pin "2") (pinfunction "2_2") (pintype "passive"))
      (node (ref "U6") (pin "13") (pinfunction "ITRIP_13") (pintype "input"))
    )
    (net (code "56") (name "Net-(U6-SR)") (class "Default")
      (node (ref "R8") (pin "2") (pinfunction "2_2") (pintype "passive"))
      (node (ref "U6") (pin "12") (pinfunction "SR_12") (pintype "input"))
    )
    (net (code "57") (name "PGND") (class "Default")
      (node (ref "C10") (pin "1") (pinfunction "1_1") (pintype "passive"))
      (node (ref "C11") (pin "1") (pinfunction "1_1") (pintype "passive"))
      (node (ref "C12") (pin "1") (pinfunction "1_1") (pintype "passive"))
      (node (ref "C13") (pin "1") (pinfunction "1_1") (pintype "passive"))
      (node (ref "C14") (pin "1") (pinfunction "1_1") (pintype "passive"))
      (node (ref "C15") (pin "1") (pinfunction "1_1") (pintype "passive"))
      (node (ref "C16") (pin "1") (pinfunction "1_1") (pintype "passive"))
      (node (ref "C17") (pin "1") (pinfunction "1_1") (pintype "passive"))
      (node (ref "C2") (pin "1") (pinfunction "1_1") (pintype "passive"))
      (node (ref "C21") (pin "1") (pinfunction "1_1") (pintype "passive"))
      (node (ref "C24") (pin "2") (pinfunction "2_2") (pintype "passive"))
      (node (ref "C26") (pin "1") (pinfunction "1_1") (pintype "passive"))
      (node (ref "C3") (pin "1") (pinfunction "1_1") (pintype "passive"))
      (node (ref "C4") (pin "1") (pinfunction "1_1") (pintype "passive"))
      (node (ref "C5") (pin "1") (pinfunction "1_1") (pintype "passive"))
      (node (ref "C9") (pin "1") (pinfunction "1_1") (pintype "passive"))
      (node (ref "J1") (pin "1") (pinfunction "GND_1") (pintype "passive"))
      (node (ref "J10") (pin "1") (pinfunction "P1_1") (pintype "passive"))
      (node (ref "R1") (pin "1") (pinfunction "1_1") (pintype "passive"))
      (node (ref "R2") (pin "1") (pinfunction "1_1") (pintype "passive"))
      (node (ref "R3") (pin "2") (pinfunction "2_2") (pintype "passive"))
      (node (ref "R4") (pin "2") (pinfunction "2_2") (pintype "passive"))
      (node (ref "R5") (pin "1") (pinfunction "1_1") (pintype "passive"))
      (node (ref "R6") (pin "1") (pinfunction "1_1") (pintype "passive"))
      (node (ref "R7") (pin "2") (pinfunction "2_2") (pintype "passive"))
      (node (ref "R8") (pin "1") (pinfunction "1_1") (pintype "passive"))
      (node (ref "R9") (pin "1") (pinfunction "1_1") (pintype "passive"))
      (node (ref "U1") (pin "15") (pinfunction "GNDb_15") (pintype "passive"))
      (node (ref "U1") (pin "9") (pinfunction "GNDb_9") (pintype "passive"))
      (node (ref "U10") (pin "2") (pinfunction "GND_2") (pintype "passive"))
      (node (ref "U2") (pin "11") (pinfunction "DIAG_11") (pintype "input"))
      (node (ref "U2") (pin "14") (pinfunction "MODE_14") (pintype "input"))
      (node (ref "U2") (pin "6") (pinfunction "GND_6") (pintype "power_in"))
      (node (ref "U2") (pin "8") (pinfunction "DRVOFF_8") (pintype "input"))
      (node (ref "U4") (pin "15") (pinfunction "GNDb_15") (pintype "passive"))
      (node (ref "U4") (pin "9") (pinfunction "GNDb_9") (pintype "passive"))
      (node (ref "U5") (pin "11") (pinfunction "DIAG_11") (pintype "input"))
      (node (ref "U5") (pin "14") (pinfunction "MODE_14") (pintype "input"))
      (node (ref "U5") (pin "6") (pinfunction "GND_6") (pintype "power_in"))
      (node (ref "U5") (pin "8") (pinfunction "DRVOFF_8") (pintype "input"))
      (node (ref "U6") (pin "11") (pinfunction "DIAG_11") (pintype "input"))
      (node (ref "U6") (pin "14") (pinfunction "MODE_14") (pintype "input"))
      (node (ref "U6") (pin "6") (pinfunction "GND_6") (pintype "power_in"))
      (node (ref "U6") (pin "8") (pinfunction "DRVOFF_8") (pintype "input"))
      (node (ref "U9") (pin "4") (pinfunction "G_4") (pintype "passive"))
    )
    (net (code "58") (name "unconnected-(J1-EN1-Pad3)") (class "Default")
      (node (ref "J1") (pin "3") (pinfunction "EN1_3") (pintype "passive"))
    )
    (net (code "59") (name "unconnected-(J1-EN2-Pad4)") (class "Default")
      (node (ref "J1") (pin "4") (pinfunction "EN2_4") (pintype "passive"))
    )
    (net (code "60") (name "unconnected-(J4-Pad6)") (class "Default")
      (node (ref "J4") (pin "6") (pintype "passive"))
    )
    (net (code "61") (name "unconnected-(J4-Pad7)") (class "Default")
      (node (ref "J4") (pin "7") (pintype "passive"))
    )
    (net (code "62") (name "unconnected-(J4-Pad8)") (class "Default")
      (node (ref "J4") (pin "8") (pintype "passive"))
    )
    (net (code "63") (name "unconnected-(J16-ID-Pad4)") (class "Default")
      (node (ref "J16") (pin "4") (pinfunction "ID_4") (pintype "passive"))
    )
    (net (code "64") (name "unconnected-(U1-ENb-Pad10)") (class "Default")
      (node (ref "U1") (pin "10") (pinfunction "ENb_10") (pintype "passive"))
    )
    (net (code "65") (name "unconnected-(U1-I.C.-Pad7)") (class "Default")
      (node (ref "U1") (pin "7") (pinfunction "I.C._7") (pintype "passive"))
    )
    (net (code "66") (name "unconnected-(U4-ENb-Pad10)") (class "Default")
      (node (ref "U4") (pin "10") (pinfunction "ENb_10") (pintype "passive"))
    )
    (net (code "67") (name "unconnected-(U4-I.C.-Pad7)") (class "Default")
      (node (ref "U4") (pin "7") (pinfunction "I.C._7") (pintype "passive"))
    )
    (net (code "68") (name "unconnected-(U7-NC-Pad1)") (class "Default")
      (node (ref "U7") (pin "1") (pinfunction "NC_1") (pintype "passive"))
    )
    (net (code "69") (name "unconnected-(U8-PA0-Pad5)") (class "Default")
      (node (ref "U8") (pin "5") (pinfunction "PA0_5") (pintype "passive"))
    )
    (net (code "70") (name "unconnected-(U8-PA3-Pad8)") (class "Default")
      (node (ref "U8") (pin "8") (pinfunction "PA3_8") (pintype "passive"))
    )
    (net (code "71") (name "unconnected-(U8-PA5-Pad10)") (class "Default")
      (node (ref "U8") (pin "10") (pinfunction "PA5_10") (pintype "passive"))
    )
    (net (code "72") (name "unconnected-(U8-PB0-Pad13)") (class "Default")
      (node (ref "U8") (pin "13") (pinfunction "PB0_13") (pintype "passive"))
    )
    (net (code "73") (name "unconnected-(U8-PF0-OSC_IN-Pad2)") (class "Default")
      (node (ref "U8") (pin "2") (pinfunction "PF0-OSC_IN_2") (pintype "passive"))
    )
    (net (code "74") (name "unconnected-(U8-PF1-OSC_OUT-Pad3)") (class "Default")
      (node (ref "U8") (pin "3") (pinfunction "PF1-OSC_OUT_3") (pintype "passive"))
    )
    (net (code "75") (name "unconnected-(U10-NC-Pad4)") (class "Default")
      (node (ref "U10") (pin "4") (pinfunction "NC_4") (pintype "passive"))
    )
  )
)
